# tort.net
KiCad netlist of a schematic drawn in EAGLE
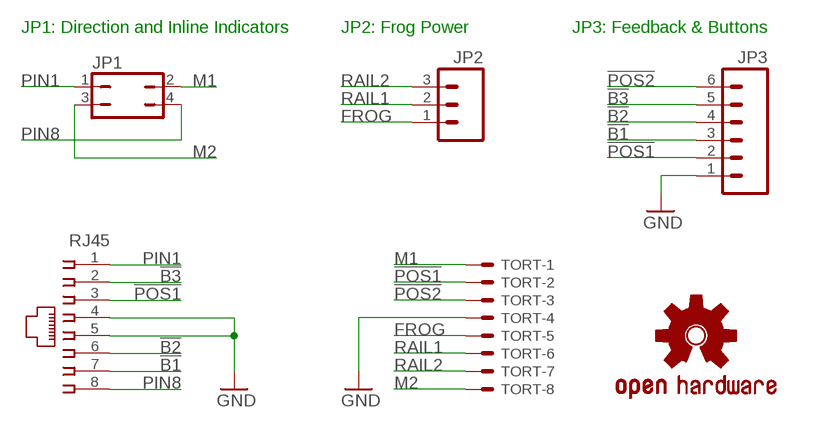
[diagram p0: schematic, sheet 1]

(export (version "E")
  (design (tool "Eeschema 10.0.6"))
  (components
    (comp (ref "JP1")
      (value "JP2Q")
      (footprint "eagle-import:JP2Q")
      (libsource (lib "eagle-import") (part "JP2Q"))
    )
    (comp (ref "JP2")
      (value "M03-SCREW-5MM")
      (footprint "eagle-import:SCREWTERMINAL-5MM-3")
      (libsource (lib "eagle-import") (part "M03-SCREW-5MM"))
    )
    (comp (ref "JP3")
      (value "M063.5MM-6")
      (footprint "eagle-import:SCREWTERMINAL-3.5MM-6")
      (libsource (lib "eagle-import") (part "M063.5MM-6"))
    )
    (comp (ref "LOGO1")
      (value "OSHW-LOGOL")
      (footprint "eagle-import:OSHW-LOGO-L")
      (libsource (lib "eagle-import") (part "OSHW-LOGOL"))
    )
    (comp (ref "RJ45")
      (value "215877-7")
      (footprint "eagle-import:215877-7")
      (libsource (lib "eagle-import") (part "215877-7"))
    )
    (comp (ref "STANDOFF1")
      (value "STAND-OFF")
      (footprint "eagle-import:STAND-OFF")
      (libsource (lib "eagle-import") (part "STAND-OFF"))
    )
    (comp (ref "TORT")
      (value "KK-156-8")
      (footprint "eagle-import:KK-156-8")
      (libsource (lib "eagle-import") (part "KK-156-8"))
    )
  )
  (nets
    (net (code "1") (name "/FROG") (class "Default")
      (node (ref "JP2") (pin "1") (pinfunction "1_1") (pintype "passive"))
      (node (ref "TORT") (pin "5") (pinfunction "S_5") (pintype "passive"))
    )
    (net (code "2") (name "/M1") (class "Default")
      (node (ref "JP1") (pin "2") (pinfunction "2_2") (pintype "passive"))
      (node (ref "TORT") (pin "1") (pinfunction "S_1") (pintype "passive"))
    )
    (net (code "3") (name "/M2") (class "Default")
      (node (ref "JP1") (pin "3") (pinfunction "3_3") (pintype "passive"))
      (node (ref "TORT") (pin "8") (pinfunction "S_8") (pintype "passive"))
    )
    (net (code "4") (name "/PIN1") (class "Default")
      (node (ref "JP1") (pin "1") (pinfunction "1_1") (pintype "passive"))
      (node (ref "RJ45") (pin "1") (pinfunction "1_1") (pintype "passive"))
    )
    (net (code "5") (name "/PIN8") (class "Default")
      (node (ref "JP1") (pin "4") (pinfunction "4_4") (pintype "passive"))
      (node (ref "RJ45") (pin "8") (pinfunction "8_8") (pintype "passive"))
    )
    (net (code "6") (name "/RAIL1") (class "Default")
      (node (ref "JP2") (pin "2") (pinfunction "2_2") (pintype "passive"))
      (node (ref "TORT") (pin "6") (pinfunction "S_6") (pintype "passive"))
    )
    (net (code "7") (name "/RAIL2") (class "Default")
      (node (ref "JP2") (pin "3") (pinfunction "3_3") (pintype "passive"))
      (node (ref "TORT") (pin "7") (pinfunction "S_7") (pintype "passive"))
    )
    (net (code "8") (name "/~{B1}") (class "Default")
      (node (ref "JP3") (pin "3") (pinfunction "3_3") (pintype "passive"))
      (node (ref "RJ45") (pin "7") (pinfunction "7_7") (pintype "passive"))
    )
    (net (code "9") (name "/~{B2}") (class "Default")
      (node (ref "JP3") (pin "4") (pinfunction "4_4") (pintype "passive"))
      (node (ref "RJ45") (pin "6") (pinfunction "6_6") (pintype "passive"))
    )
    (net (code "10") (name "/~{B3}") (class "Default")
      (node (ref "JP3") (pin "5") (pinfunction "5_5") (pintype "passive"))
      (node (ref "RJ45") (pin "2") (pinfunction "2_2") (pintype "passive"))
    )
    (net (code "11") (name "/~{POS1}") (class "Default")
      (node (ref "JP3") (pin "2") (pinfunction "2_2") (pintype "passive"))
      (node (ref "RJ45") (pin "3") (pinfunction "3_3") (pintype "passive"))
      (node (ref "TORT") (pin "2") (pinfunction "S_2") (pintype "passive"))
    )
    (net (code "12") (name "/~{POS2}") (class "Default")
      (node (ref "JP3") (pin "6") (pinfunction "6_6") (pintype "passive"))
      (node (ref "TORT") (pin "3") (pinfunction "S_3") (pintype "passive"))
    )
    (net (code "13") (name "GND") (class "Default")
      (node (ref "JP3") (pin "1") (pinfunction "1_1") (pintype "passive"))
      (node (ref "RJ45") (pin "4") (pinfunction "4_4") (pintype "passive"))
      (node (ref "RJ45") (pin "5") (pinfunction "5_5") (pintype "passive"))
      (node (ref "TORT") (pin "4") (pinfunction "S_4") (pintype "passive"))
    )
  )
)
